# Basic_flex_IMU.net
KiCad netlist of a schematic drawn in Altium Designer
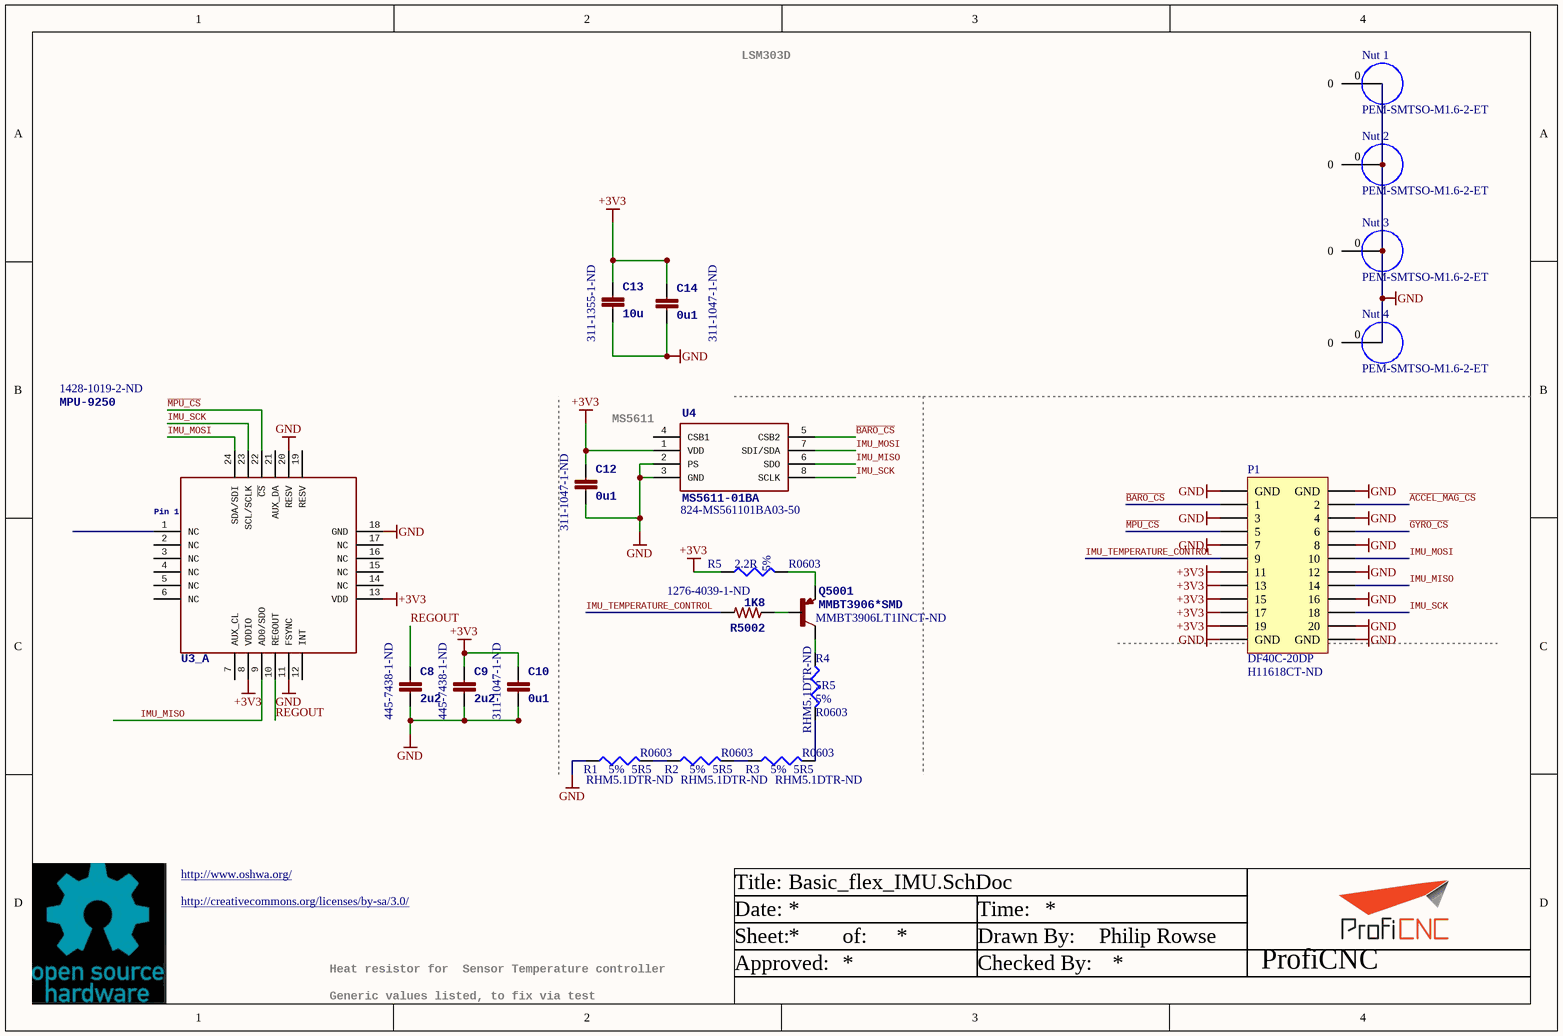
[diagram p0: Basic_flex_IMU.SchDoc]

(export (version "E")
  (design (tool "Eeschema 10.0.6"))
  (components
    (comp (ref "C8")
      (value "2u2")
      (footprint "0603-CAP")
      (description "Capacitor, 2.2uF, 16V, 10%, X6S, 0603, Ceramic")
      (fields
        (field (name "PARTNO") "C1608X6S1C225K080AC")
        (field (name "SUPPLIER PART NUMBER 1") "445-7438-1-ND")
        (field (name "3DR_PARTNO") "ECM0619")
      )
      (libsource (lib "lib_pixhawk") (part "CAPACITOR-0603"))
    )
    (comp (ref "C9")
      (value "2u2")
      (footprint "0603-CAP")
      (description "Capacitor, 2.2uF, 16V, 10%, X6S, 0603, Ceramic")
      (fields
        (field (name "PARTNO") "C1608X6S1C225K080AC")
        (field (name "SUPPLIER PART NUMBER 1") "445-7438-1-ND")
        (field (name "3DR_PARTNO") "ECM0619")
      )
      (libsource (lib "lib_pixhawk") (part "CAPACITOR-0603"))
    )
    (comp (ref "C10")
      (value "0u1")
      (footprint "0402-CAP")
      (description "Capacitor, 0.1uF, 16V, Y5V, 0402, Ceramic")
      (fields
        (field (name "PARTNO") "CC0402ZRY5V7BB104")
        (field (name "SUPPLIER PART NUMBER 1") "311-1047-1-ND")
        (field (name "3DR_PARTNO") "ECM0700")
      )
      (libsource (lib "lib_pixhawk") (part "CAPACITOR-0402"))
    )
    (comp (ref "C12")
      (value "0u1")
      (footprint "0402-CAP")
      (description "Capacitor, 0.1uF, 16V, Y5V, 0402, Ceramic")
      (fields
        (field (name "PARTNO") "CC0402ZRY5V7BB104")
        (field (name "SUPPLIER PART NUMBER 1") "311-1047-1-ND")
        (field (name "3DR_PARTNO") "ECM0700")
      )
      (libsource (lib "lib_pixhawk") (part "CAPACITOR-0402"))
    )
    (comp (ref "C13")
      (value "10u")
      (footprint "0805-CAP")
      (description "Capacitor, 10uF, 10V, Y5V, 0805, Ceramic")
      (fields
        (field (name "PARTNO") "CC0805ZKY5V6BB106")
        (field (name "SUPPLIER PART NUMBER 1") "311-1355-1-ND")
        (field (name "3DR_PARTNO") "ECM0713")
      )
      (libsource (lib "lib_pixhawk") (part "CAPACITOR-0805"))
    )
    (comp (ref "C14")
      (value "0u1")
      (footprint "0402-CAP")
      (description "Capacitor, 0.1uF, 16V, Y5V, 0402, Ceramic")
      (fields
        (field (name "PARTNO") "CC0402ZRY5V7BB104")
        (field (name "SUPPLIER PART NUMBER 1") "311-1047-1-ND")
        (field (name "3DR_PARTNO") "ECM0700")
      )
      (libsource (lib "lib_pixhawk") (part "CAPACITOR-0402"))
    )
    (comp (ref "Nut 1")
      (value "PEM-SMTSO-M1.6-2-ET")
      (footprint "PEM-SMTSO-M1.6-2-ET")
      (description "Fastener, M1.6x2mm, SMTSO, Carbon Steel")
      (fields (field (name "3DR_PARTNO") "PRT0438"))
      (libsource (lib "pixhawk2") (part "PEM-SMTSO-M1.6-2-ET"))
    )
    (comp (ref "Nut 2")
      (value "PEM-SMTSO-M1.6-2-ET")
      (footprint "PEM-SMTSO-M1.6-2-ET")
      (description "Fastener, M1.6x2mm, SMTSO, Carbon Steel")
      (fields (field (name "3DR_PARTNO") "PRT0438"))
      (libsource (lib "pixhawk2") (part "PEM-SMTSO-M1.6-2-ET"))
    )
    (comp (ref "Nut 3")
      (value "PEM-SMTSO-M1.6-2-ET")
      (footprint "PEM-SMTSO-M1.6-2-ET")
      (description "Fastener, M1.6x2mm, SMTSO, Carbon Steel")
      (fields (field (name "3DR_PARTNO") "PRT0438"))
      (libsource (lib "pixhawk2") (part "PEM-SMTSO-M1.6-2-ET"))
    )
    (comp (ref "Nut 4")
      (value "PEM-SMTSO-M1.6-2-ET")
      (footprint "PEM-SMTSO-M1.6-2-ET")
      (description "Fastener, M1.6x2mm, SMTSO, Carbon Steel")
      (fields (field (name "3DR_PARTNO") "PRT0438"))
      (libsource (lib "pixhawk2") (part "PEM-SMTSO-M1.6-2-ET"))
    )
    (comp (ref "P1")
      (value "DF40C-20DP")
      (footprint "DF40C-20-DP")
      (description "Connector, HDR, 20Pos, 0.4mm, SMD, GOLD")
      (fields
        (field (name "SUPPLIER PART NUMBER 1") "H11618CT-ND")
        (field (name "3DR_PARTNO") "ECM0510")
        (field (name "PUBLISHER") "Altium Limited")
      )
      (libsource (lib "pixhawk2") (part "DF40C-20DP"))
    )
    (comp (ref "Q5001")
      (value "MMBT3906*SMD")
      (footprint "SOT23-BEC")
      (description "TRANSISTOR SWITCHING PNP SOT-23")
      (fields
        (field (name "SUPPLIER PART NUMBER 1") "MMBT3906LT1INCT-ND")
        (field (name "3DR_PARTNO") "ECM0833")
        (field (name "PARTNO") "MMBT 3906 LT1")
      )
      (libsource (lib "transistor-pnp") (part "MMBT3906*SMD"))
    )
    (comp (ref "R1")
      (value "5R5")
      (footprint "R0603")
      (description "RES SMD 5.1 OHM 5% 1/4W 0603")
      (fields
        (field (name "TOLERANCE") "5%")
        (field (name "SUPPLIER PART NUMBER 1") "RHM5.1DTR-ND")
        (field (name "Comment") "Resistor")
      )
      (libsource (lib "3DR") (part "Resistor"))
    )
    (comp (ref "R2")
      (value "5R5")
      (footprint "R0603")
      (description "RES SMD 5.1 OHM 5% 1/4W 0603")
      (fields
        (field (name "TOLERANCE") "5%")
        (field (name "SUPPLIER PART NUMBER 1") "RHM5.1DTR-ND")
        (field (name "Comment") "Resistor")
      )
      (libsource (lib "3DR") (part "Resistor"))
    )
    (comp (ref "R3")
      (value "5R5")
      (footprint "R0603")
      (description "RES SMD 5.1 OHM 5% 1/4W 0603")
      (fields
        (field (name "TOLERANCE") "5%")
        (field (name "SUPPLIER PART NUMBER 1") "RHM5.1DTR-ND")
        (field (name "Comment") "Resistor")
      )
      (libsource (lib "3DR") (part "Resistor"))
    )
    (comp (ref "R4")
      (value "5R5")
      (footprint "R0603")
      (description "RES SMD 5.1 OHM 5% 1/4W 0603")
      (fields
        (field (name "TOLERANCE") "5%")
        (field (name "SUPPLIER PART NUMBER 1") "RHM5.1DTR-ND")
        (field (name "Comment") "Resistor")
      )
      (libsource (lib "3DR") (part "Resistor"))
    )
    (comp (ref "R5")
      (value "2.2R")
      (footprint "R0603")
      (description "RES SMD 5.1 OHM 5% 1/4W 0603")
      (fields (field (name "TOLERANCE") "5%") (field (name "Comment") "Resistor"))
      (libsource (lib "3DR") (part "Resistor"))
    )
    (comp (ref "R5002")
      (value "1K8")
      (footprint "0402-RES")
      (description "RES 1.8K OHM 1/16W 1% 0402")
      (fields
        (field (name "PARTNO") "RC1005F182CS")
        (field (name "SUPPLIER PART NUMBER 1") "1276-4039-1-ND")
        (field (name "3DR_PARTNO") "ECM0807")
      )
      (libsource (lib "pixhawk2") (part "RESISTOR0402-RES"))
    )
    (comp (ref "U3_A")
      (value "MPU-9250")
      (footprint "MPU-9250")
      (fields (field (name "PIN 1") "Pin 1") (field (name "SUPPLIER PART NUMBER 1") "1428-1019-2-ND"))
      (libsource (lib "pixhawk2") (part "MPU-6500"))
    )
    (comp (ref "U4")
      (value "MS5611-01BA")
      (footprint "MS5611-01BA")
      (description "Board, Digital pressure sensor I2C/SPI")
      (fields
        (field (name "SUPPLIER PART NUMBER 1") "824-MS561101BA03-50")
        (field (name "3DR_PARTNO") "ECM0835")
      )
      (libsource (lib "pixhawk2") (part "MS5611-01BA"))
    )
  )
  (nets
    (net (code "1") (name "+3V3") (class "Default")
      (node (ref "C10") (pin "P$1") (pinfunction "1_P$1") (pintype "passive"))
      (node (ref "C12") (pin "P$1") (pinfunction "1_P$1") (pintype "passive"))
      (node (ref "C13") (pin "P$1") (pinfunction "1_P$1") (pintype "passive"))
      (node (ref "C14") (pin "P$1") (pinfunction "1_P$1") (pintype "passive"))
      (node (ref "C9") (pin "P$1") (pinfunction "1_P$1") (pintype "passive"))
      (node (ref "P1") (pin "11") (pinfunction "11_11") (pintype "passive"))
      (node (ref "P1") (pin "13") (pinfunction "13_13") (pintype "passive"))
      (node (ref "P1") (pin "15") (pinfunction "15_15") (pintype "passive"))
      (node (ref "P1") (pin "17") (pinfunction "17_17") (pintype "passive"))
      (node (ref "P1") (pin "19") (pinfunction "19_19") (pintype "passive"))
      (node (ref "R5") (pin "1") (pinfunction "1_1") (pintype "passive"))
      (node (ref "U3_A") (pin "13") (pinfunction "VDD_13") (pintype "passive"))
      (node (ref "U3_A") (pin "8") (pinfunction "VDDIO_8") (pintype "passive"))
      (node (ref "U4") (pin "1") (pinfunction "VDD_1") (pintype "passive"))
    )
    (net (code "2") (name "/IMU_MISO") (class "Default")
      (node (ref "P1") (pin "14") (pinfunction "14_14") (pintype "passive"))
      (node (ref "U3_A") (pin "9") (pinfunction "AD0/SDO_9") (pintype "passive"))
      (node (ref "U4") (pin "6") (pinfunction "SDO_6") (pintype "passive"))
    )
    (net (code "3") (name "/IMU_MOSI") (class "Default")
      (node (ref "P1") (pin "10") (pinfunction "10_10") (pintype "passive"))
      (node (ref "U3_A") (pin "24") (pinfunction "SDA/SDI_24") (pintype "passive"))
      (node (ref "U4") (pin "7") (pinfunction "SDI/SDA_7") (pintype "passive"))
    )
    (net (code "4") (name "/IMU_SCK") (class "Default")
      (node (ref "P1") (pin "18") (pinfunction "18_18") (pintype "passive"))
      (node (ref "U3_A") (pin "23") (pinfunction "SCL/SCLK_23") (pintype "passive"))
      (node (ref "U4") (pin "8") (pinfunction "SCLK_8") (pintype "passive"))
    )
    (net (code "5") (name "/IMU_TEMPERATURE_CONTROL") (class "Default")
      (node (ref "P1") (pin "9") (pinfunction "9_9") (pintype "passive"))
      (node (ref "R5002") (pin "P$2") (pinfunction "2_P$2") (pintype "passive"))
    )
    (net (code "6") (name "/REGOUT") (class "Default")
      (node (ref "C8") (pin "P$1") (pinfunction "1_P$1") (pintype "passive"))
      (node (ref "U3_A") (pin "10") (pinfunction "REGOUT_10") (pintype "passive"))
    )
    (net (code "7") (name "/~{ACCEL_MAG_CS}") (class "Default")
      (node (ref "P1") (pin "2") (pinfunction "2_2") (pintype "passive"))
    )
    (net (code "8") (name "/~{BARO_CS}") (class "Default")
      (node (ref "P1") (pin "1") (pinfunction "1_1") (pintype "passive"))
      (node (ref "U4") (pin "5") (pinfunction "CSB2_5") (pintype "passive"))
    )
    (net (code "9") (name "/~{GYRO_CS}") (class "Default")
      (node (ref "P1") (pin "6") (pinfunction "6_6") (pintype "passive"))
    )
    (net (code "10") (name "/~{MPU_CS}") (class "Default")
      (node (ref "P1") (pin "5") (pinfunction "5_5") (pintype "passive"))
      (node (ref "U3_A") (pin "22") (pinfunction "~{CS}_22") (pintype "passive"))
    )
    (net (code "11") (name "GND") (class "Default")
      (node (ref "C10") (pin "P$2") (pinfunction "2_P$2") (pintype "passive"))
      (node (ref "C12") (pin "P$2") (pinfunction "2_P$2") (pintype "passive"))
      (node (ref "C13") (pin "P$2") (pinfunction "2_P$2") (pintype "passive"))
      (node (ref "C14") (pin "P$2") (pinfunction "2_P$2") (pintype "passive"))
      (node (ref "C8") (pin "P$2") (pinfunction "2_P$2") (pintype "passive"))
      (node (ref "C9") (pin "P$2") (pinfunction "2_P$2") (pintype "passive"))
      (node (ref "Nut 1") (pin "0") (pinfunction "0_0") (pintype "passive"))
      (node (ref "Nut 2") (pin "0") (pinfunction "0_0") (pintype "passive"))
      (node (ref "Nut 3") (pin "0") (pinfunction "0_0") (pintype "passive"))
      (node (ref "Nut 4") (pin "0") (pinfunction "0_0") (pintype "passive"))
      (node (ref "P1") (pin "12") (pinfunction "12_12") (pintype "passive"))
      (node (ref "P1") (pin "16") (pinfunction "16_16") (pintype "passive"))
      (node (ref "P1") (pin "20") (pinfunction "20_20") (pintype "passive"))
      (node (ref "P1") (pin "21") (pinfunction "GND_21") (pintype "passive"))
      (node (ref "P1") (pin "22") (pinfunction "GND_22") (pintype "passive"))
      (node (ref "P1") (pin "23") (pinfunction "GND_23") (pintype "passive"))
      (node (ref "P1") (pin "24") (pinfunction "GND_24") (pintype "passive"))
      (node (ref "P1") (pin "3") (pinfunction "3_3") (pintype "passive"))
      (node (ref "P1") (pin "4") (pinfunction "4_4") (pintype "passive"))
      (node (ref "P1") (pin "7") (pinfunction "7_7") (pintype "passive"))
      (node (ref "P1") (pin "8") (pinfunction "8_8") (pintype "passive"))
      (node (ref "R1") (pin "1") (pinfunction "1_1") (pintype "passive"))
      (node (ref "U3_A") (pin "11") (pinfunction "FSYNC_11") (pintype "passive"))
      (node (ref "U3_A") (pin "18") (pinfunction "GND_18") (pintype "passive"))
      (node (ref "U3_A") (pin "20") (pinfunction "RESV_20") (pintype "passive"))
      (node (ref "U4") (pin "2") (pinfunction "PS_2") (pintype "passive"))
      (node (ref "U4") (pin "3") (pinfunction "GND_3") (pintype "passive"))
    )
    (net (code "12") (name "Net-(Q5001-PadC)") (class "Default")
      (node (ref "Q5001") (pin "C") (pinfunction "C_C") (pintype "passive"))
      (node (ref "R4") (pin "1") (pinfunction "1_1") (pintype "passive"))
    )
    (net (code "13") (name "Net-(Q5001-PadE)") (class "Default")
      (node (ref "Q5001") (pin "E") (pinfunction "E_E") (pintype "passive"))
      (node (ref "R5") (pin "2") (pinfunction "2_2") (pintype "passive"))
    )
    (net (code "14") (name "Net-(R1-Pad2)") (class "Default")
      (node (ref "R1") (pin "2") (pinfunction "2_2") (pintype "passive"))
      (node (ref "R2") (pin "1") (pinfunction "1_1") (pintype "passive"))
    )
    (net (code "15") (name "Net-(R2-Pad2)") (class "Default")
      (node (ref "R2") (pin "2") (pinfunction "2_2") (pintype "passive"))
      (node (ref "R3") (pin "1") (pinfunction "1_1") (pintype "passive"))
    )
    (net (code "16") (name "Net-(R3-Pad2)") (class "Default")
      (node (ref "R3") (pin "2") (pinfunction "2_2") (pintype "passive"))
      (node (ref "R4") (pin "2") (pinfunction "2_2") (pintype "passive"))
    )
    (net (code "17") (name "Net-(R5002-1)") (class "Default")
      (node (ref "Q5001") (pin "B") (pinfunction "B_B") (pintype "passive"))
      (node (ref "R5002") (pin "P$1") (pinfunction "1_P$1") (pintype "passive"))
    )
    (net (code "18") (name "unconnected-(U3_A-AUX_CL-Pad7)") (class "Default")
      (node (ref "U3_A") (pin "7") (pinfunction "AUX_CL_7") (pintype "passive"))
    )
    (net (code "19") (name "unconnected-(U3_A-AUX_DA-Pad21)") (class "Default")
      (node (ref "U3_A") (pin "21") (pinfunction "AUX_DA_21") (pintype "passive"))
    )
    (net (code "20") (name "unconnected-(U3_A-INT-Pad12)") (class "Default")
      (node (ref "U3_A") (pin "12") (pinfunction "INT_12") (pintype "passive"))
    )
    (net (code "21") (name "unconnected-(U3_A-NC-Pad1)") (class "Default")
      (node (ref "U3_A") (pin "1") (pinfunction "NC_1") (pintype "passive"))
    )
    (net (code "22") (name "unconnected-(U3_A-NC-Pad2)") (class "Default")
      (node (ref "U3_A") (pin "2") (pinfunction "NC_2") (pintype "passive"))
    )
    (net (code "23") (name "unconnected-(U3_A-NC-Pad3)") (class "Default")
      (node (ref "U3_A") (pin "3") (pinfunction "NC_3") (pintype "passive"))
    )
    (net (code "24") (name "unconnected-(U3_A-NC-Pad4)") (class "Default")
      (node (ref "U3_A") (pin "4") (pinfunction "NC_4") (pintype "passive"))
    )
    (net (code "25") (name "unconnected-(U3_A-NC-Pad5)") (class "Default")
      (node (ref "U3_A") (pin "5") (pinfunction "NC_5") (pintype "passive"))
    )
    (net (code "26") (name "unconnected-(U3_A-NC-Pad6)") (class "Default")
      (node (ref "U3_A") (pin "6") (pinfunction "NC_6") (pintype "passive"))
    )
    (net (code "27") (name "unconnected-(U3_A-NC-Pad14)") (class "Default")
      (node (ref "U3_A") (pin "14") (pinfunction "NC_14") (pintype "passive"))
    )
    (net (code "28") (name "unconnected-(U3_A-NC-Pad15)") (class "Default")
      (node (ref "U3_A") (pin "15") (pinfunction "NC_15") (pintype "passive"))
    )
    (net (code "29") (name "unconnected-(U3_A-NC-Pad16)") (class "Default")
      (node (ref "U3_A") (pin "16") (pinfunction "NC_16") (pintype "passive"))
    )
    (net (code "30") (name "unconnected-(U3_A-NC-Pad17)") (class "Default")
      (node (ref "U3_A") (pin "17") (pinfunction "NC_17") (pintype "passive"))
    )
    (net (code "31") (name "unconnected-(U3_A-RESV-Pad19)") (class "Default")
      (node (ref "U3_A") (pin "19") (pinfunction "RESV_19") (pintype "passive"))
    )
    (net (code "32") (name "unconnected-(U4-CSB1-Pad4)") (class "Default")
      (node (ref "U4") (pin "4") (pinfunction "CSB1_4") (pintype "passive"))
    )
  )
)
